# Robot_Board_v001.net
KiCad netlist of a schematic drawn in EAGLE
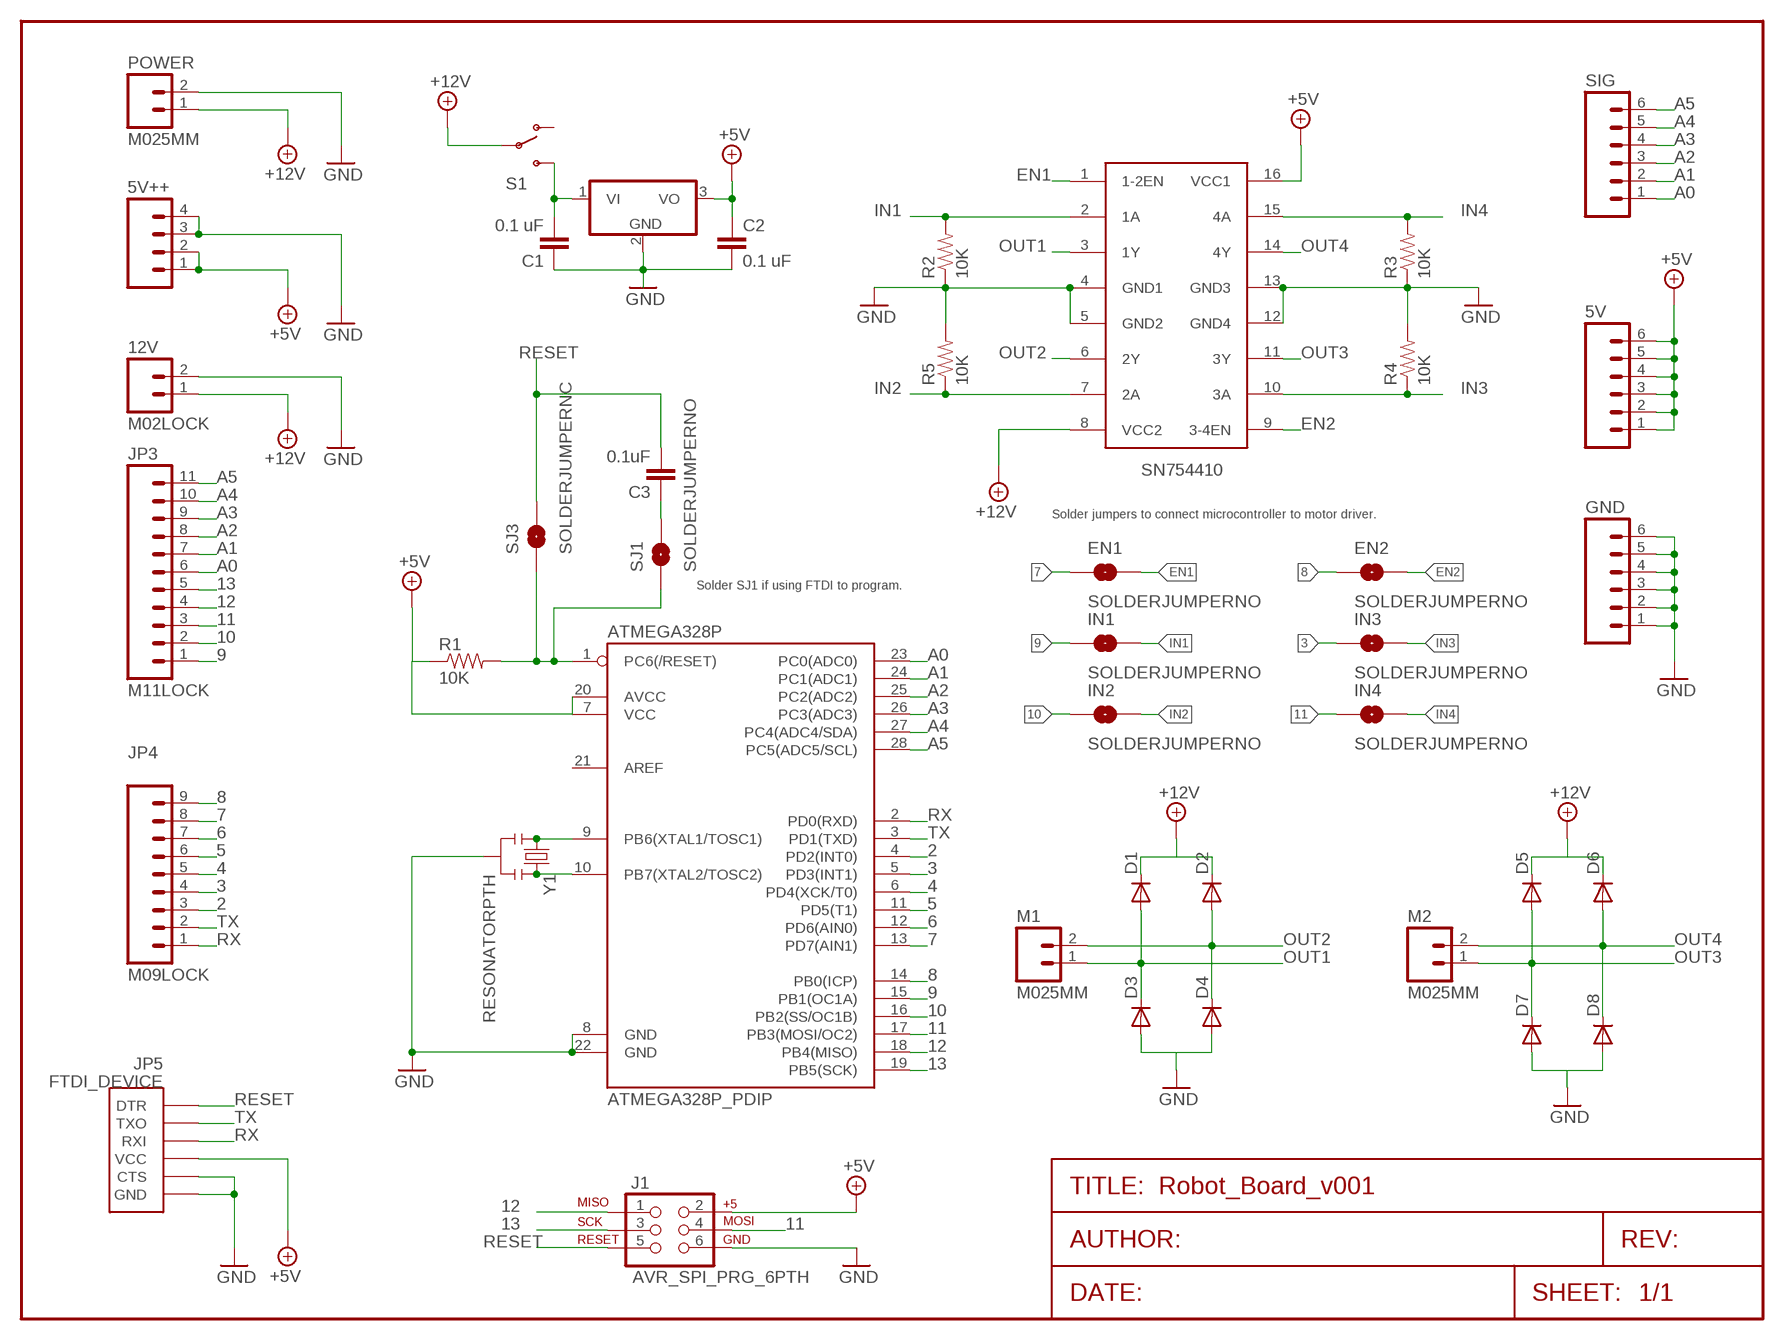
[diagram p0: schematic, sheet 1]

(export (version "E")
  (design (tool "Eeschema 10.0.6"))
  (components
    (comp (ref "5V")
      (value "M06SIP")
      (footprint "eagle-import:1X06")
      (libsource (lib "eagle-import") (part "M06SIP"))
    )
    (comp (ref "5V++")
      (value "M04LOCK")
      (footprint "eagle-import:1X04_LOCK")
      (libsource (lib "eagle-import") (part "M04LOCK"))
    )
    (comp (ref "12V")
      (value "M02LOCK")
      (footprint "eagle-import:1X02_LOCK")
      (libsource (lib "eagle-import") (part "M02LOCK"))
    )
    (comp (ref "7805")
      (value "7805TV")
      (footprint "eagle-import:TO220V")
      (libsource (lib "eagle-import") (part "78TV05"))
    )
    (comp (ref "ATMEGA328P")
      (value "ATMEGA328P_PDIP")
      (footprint "eagle-import:DIL28-3")
      (libsource (lib "eagle-import") (part "ATMEGA328P_PDIP"))
    )
    (comp (ref "C1")
      (value "0.1 uF")
      (footprint "eagle-import:CAP-PTH-5MM")
      (libsource (lib "eagle-import") (part "CAPPTH1"))
    )
    (comp (ref "C2")
      (value "0.1 uF")
      (footprint "eagle-import:CAP-PTH-5MM")
      (libsource (lib "eagle-import") (part "CAPPTH1"))
    )
    (comp (ref "C3")
      (value "0.1uF")
      (footprint "eagle-import:CAP-PTH-5MM")
      (libsource (lib "eagle-import") (part "CAPPTH1"))
    )
    (comp (ref "D1")
      (value "DIODEPTH")
      (footprint "eagle-import:DIODE-1N4001")
      (libsource (lib "eagle-import") (part "DIODEPTH"))
    )
    (comp (ref "D2")
      (value "DIODEPTH")
      (footprint "eagle-import:DIODE-1N4001")
      (libsource (lib "eagle-import") (part "DIODEPTH"))
    )
    (comp (ref "D3")
      (value "DIODEPTH")
      (footprint "eagle-import:DIODE-1N4001")
      (libsource (lib "eagle-import") (part "DIODEPTH"))
    )
    (comp (ref "D4")
      (value "DIODEPTH")
      (footprint "eagle-import:DIODE-1N4001")
      (libsource (lib "eagle-import") (part "DIODEPTH"))
    )
    (comp (ref "D5")
      (value "DIODEPTH")
      (footprint "eagle-import:DIODE-1N4001")
      (libsource (lib "eagle-import") (part "DIODEPTH"))
    )
    (comp (ref "D6")
      (value "DIODEPTH")
      (footprint "eagle-import:DIODE-1N4001")
      (libsource (lib "eagle-import") (part "DIODEPTH"))
    )
    (comp (ref "D7")
      (value "DIODEPTH")
      (footprint "eagle-import:DIODE-1N4001")
      (libsource (lib "eagle-import") (part "DIODEPTH"))
    )
    (comp (ref "D8")
      (value "DIODEPTH")
      (footprint "eagle-import:DIODE-1N4001")
      (libsource (lib "eagle-import") (part "DIODEPTH"))
    )
    (comp (ref "EN1")
      (value "SOLDERJUMPERNO")
      (footprint "eagle-import:SJ_2S-NO")
      (libsource (lib "eagle-import") (part "SOLDERJUMPERNO"))
    )
    (comp (ref "EN2")
      (value "SOLDERJUMPERNO")
      (footprint "eagle-import:SJ_2S-NO")
      (libsource (lib "eagle-import") (part "SOLDERJUMPERNO"))
    )
    (comp (ref "GND")
      (value "M06SIP")
      (footprint "eagle-import:1X06")
      (libsource (lib "eagle-import") (part "M06SIP"))
    )
    (comp (ref "IN1")
      (value "SOLDERJUMPERNO")
      (footprint "eagle-import:SJ_2S-NO")
      (libsource (lib "eagle-import") (part "SOLDERJUMPERNO"))
    )
    (comp (ref "IN2")
      (value "SOLDERJUMPERNO")
      (footprint "eagle-import:SJ_2S-NO")
      (libsource (lib "eagle-import") (part "SOLDERJUMPERNO"))
    )
    (comp (ref "IN3")
      (value "SOLDERJUMPERNO")
      (footprint "eagle-import:SJ_2S-NO")
      (libsource (lib "eagle-import") (part "SOLDERJUMPERNO"))
    )
    (comp (ref "IN4")
      (value "SOLDERJUMPERNO")
      (footprint "eagle-import:SJ_2S-NO")
      (libsource (lib "eagle-import") (part "SOLDERJUMPERNO"))
    )
    (comp (ref "J1")
      (value "AVR_SPI_PRG_6PTH")
      (footprint "eagle-import:2X3")
      (libsource (lib "eagle-import") (part "AVR_SPI_PRG_6PTH"))
    )
    (comp (ref "JP3")
      (value "M11LOCK")
      (footprint "eagle-import:1X11_LOCK")
      (libsource (lib "eagle-import") (part "M11LOCK"))
    )
    (comp (ref "JP4")
      (value "M09LOCK")
      (footprint "eagle-import:1X09_LOCK")
      (libsource (lib "eagle-import") (part "M09LOCK"))
    )
    (comp (ref "JP5")
      (value "FTDI_DEVICE")
      (footprint "eagle-import:FTDI_DEVICE_SIDE")
      (libsource (lib "eagle-import") (part "FTDI_DEVICE"))
    )
    (comp (ref "M1")
      (value "M025MM")
      (footprint "eagle-import:SCREWTERMINAL-5MM-2")
      (libsource (lib "eagle-import") (part "M025MM"))
    )
    (comp (ref "M2")
      (value "M025MM")
      (footprint "eagle-import:SCREWTERMINAL-5MM-2")
      (libsource (lib "eagle-import") (part "M025MM"))
    )
    (comp (ref "POWER")
      (value "M025MM")
      (footprint "eagle-import:SCREWTERMINAL-5MM-2")
      (libsource (lib "eagle-import") (part "M025MM"))
    )
    (comp (ref "R1")
      (value "10K")
      (footprint "eagle-import:AXIAL-0.4")
      (libsource (lib "eagle-import") (part "RESISTORPTH-1/4W"))
    )
    (comp (ref "R2")
      (value "10K")
      (footprint "eagle-import:AXIAL-0.4")
      (libsource (lib "eagle-import") (part "RESISTORPTH-1/4W"))
    )
    (comp (ref "R3")
      (value "10K")
      (footprint "eagle-import:AXIAL-0.4")
      (libsource (lib "eagle-import") (part "RESISTORPTH-1/4W"))
    )
    (comp (ref "R4")
      (value "10K")
      (footprint "eagle-import:AXIAL-0.4")
      (libsource (lib "eagle-import") (part "RESISTORPTH-1/4W"))
    )
    (comp (ref "R5")
      (value "10K")
      (footprint "eagle-import:AXIAL-0.4")
      (libsource (lib "eagle-import") (part "RESISTORPTH-1/4W"))
    )
    (comp (ref "S1")
      (value "SWITCH-SPDTPTH")
      (footprint "eagle-import:SWITCH-SPDT")
      (libsource (lib "eagle-import") (part "SWITCH-SPDTPTH"))
    )
    (comp (ref "SIG")
      (value "M06SIP")
      (footprint "eagle-import:1X06")
      (libsource (lib "eagle-import") (part "M06SIP"))
    )
    (comp (ref "SJ1")
      (value "SOLDERJUMPERNO")
      (footprint "eagle-import:SJ_2S-NO")
      (libsource (lib "eagle-import") (part "SOLDERJUMPERNO"))
    )
    (comp (ref "SJ3")
      (value "SOLDERJUMPERNC")
      (footprint "eagle-import:SJ_2S")
      (libsource (lib "eagle-import") (part "SOLDERJUMPERNC"))
    )
    (comp (ref "SN754410")
      (value "L293D")
      (footprint "eagle-import:DIL16")
      (libsource (lib "eagle-import") (part "L293D"))
    )
    (comp (ref "Y1")
      (value "RESONATORPTH")
      (footprint "eagle-import:RESONATOR-PTH")
      (libsource (lib "eagle-import") (part "RESONATORPTH"))
    )
  )
  (nets
    (net (code "1") (name "+5V") (class "Default")
      (node (ref "5V") (pin "1") (pinfunction "1_1") (pintype "passive"))
      (node (ref "5V") (pin "2") (pinfunction "2_2") (pintype "passive"))
      (node (ref "5V") (pin "3") (pinfunction "3_3") (pintype "passive"))
      (node (ref "5V") (pin "4") (pinfunction "4_4") (pintype "passive"))
      (node (ref "5V") (pin "5") (pinfunction "5_5") (pintype "passive"))
      (node (ref "5V") (pin "6") (pinfunction "6_6") (pintype "passive"))
      (node (ref "5V++") (pin "1") (pinfunction "1_1") (pintype "passive"))
      (node (ref "5V++") (pin "2") (pinfunction "2_2") (pintype "passive"))
      (node (ref "7805") (pin "3") (pinfunction "VO_3") (pintype "passive"))
      (node (ref "ATMEGA328P") (pin "20") (pinfunction "AVCC_20") (pintype "bidirectional"))
      (node (ref "ATMEGA328P") (pin "7") (pinfunction "VCC_7") (pintype "bidirectional"))
      (node (ref "C2") (pin "1") (pinfunction "1_1") (pintype "passive"))
      (node (ref "J1") (pin "2") (pinfunction "2_2") (pintype "passive"))
      (node (ref "JP5") (pin "P$4") (pinfunction "VCC_P$4") (pintype "bidirectional"))
      (node (ref "R1") (pin "P$1") (pinfunction "1_P$1") (pintype "passive"))
      (node (ref "SN754410") (pin "16") (pinfunction "VCC1_16") (pintype "power_in"))
    )
    (net (code "2") (name "+12V") (class "Default")
      (node (ref "12V") (pin "1") (pinfunction "1_1") (pintype "passive"))
      (node (ref "D1") (pin "C") (pinfunction "C_C") (pintype "passive"))
      (node (ref "D2") (pin "C") (pinfunction "C_C") (pintype "passive"))
      (node (ref "D5") (pin "C") (pinfunction "C_C") (pintype "passive"))
      (node (ref "D6") (pin "C") (pinfunction "C_C") (pintype "passive"))
      (node (ref "POWER") (pin "1") (pinfunction "1_1") (pintype "passive"))
      (node (ref "S1") (pin "2") (pinfunction "P_2") (pintype "passive"))
      (node (ref "SN754410") (pin "8") (pinfunction "VCC2_8") (pintype "power_in"))
    )
    (net (code "3") (name "/2") (class "Default")
      (node (ref "ATMEGA328P") (pin "4") (pinfunction "PD2(INT0)_4") (pintype "bidirectional"))
      (node (ref "JP4") (pin "3") (pinfunction "3_3") (pintype "passive"))
    )
    (net (code "4") (name "/4") (class "Default")
      (node (ref "ATMEGA328P") (pin "6") (pinfunction "PD4(XCK/T0)_6") (pintype "bidirectional"))
      (node (ref "JP4") (pin "5") (pinfunction "5_5") (pintype "passive"))
    )
    (net (code "5") (name "/5") (class "Default")
      (node (ref "ATMEGA328P") (pin "11") (pinfunction "PD5(T1)_11") (pintype "bidirectional"))
      (node (ref "JP4") (pin "6") (pinfunction "6_6") (pintype "passive"))
    )
    (net (code "6") (name "/6") (class "Default")
      (node (ref "ATMEGA328P") (pin "12") (pinfunction "PD6(AIN0)_12") (pintype "bidirectional"))
      (node (ref "JP4") (pin "7") (pinfunction "7_7") (pintype "passive"))
    )
    (net (code "7") (name "/12") (class "Default")
      (node (ref "ATMEGA328P") (pin "18") (pinfunction "PB4(MISO)_18") (pintype "bidirectional"))
      (node (ref "J1") (pin "1") (pinfunction "1_1") (pintype "passive"))
      (node (ref "JP3") (pin "4") (pinfunction "4_4") (pintype "passive"))
    )
    (net (code "8") (name "/13") (class "Default")
      (node (ref "ATMEGA328P") (pin "19") (pinfunction "PB5(SCK)_19") (pintype "bidirectional"))
      (node (ref "J1") (pin "3") (pinfunction "3_3") (pintype "passive"))
      (node (ref "JP3") (pin "5") (pinfunction "5_5") (pintype "passive"))
    )
    (net (code "9") (name "/A0") (class "Default")
      (node (ref "ATMEGA328P") (pin "23") (pinfunction "PC0(ADC0)_23") (pintype "bidirectional"))
      (node (ref "JP3") (pin "6") (pinfunction "6_6") (pintype "passive"))
      (node (ref "SIG") (pin "1") (pinfunction "1_1") (pintype "passive"))
    )
    (net (code "10") (name "/A1") (class "Default")
      (node (ref "ATMEGA328P") (pin "24") (pinfunction "PC1(ADC1)_24") (pintype "bidirectional"))
      (node (ref "JP3") (pin "7") (pinfunction "7_7") (pintype "passive"))
      (node (ref "SIG") (pin "2") (pinfunction "2_2") (pintype "passive"))
    )
    (net (code "11") (name "/A2") (class "Default")
      (node (ref "ATMEGA328P") (pin "25") (pinfunction "PC2(ADC2)_25") (pintype "bidirectional"))
      (node (ref "JP3") (pin "8") (pinfunction "8_8") (pintype "passive"))
      (node (ref "SIG") (pin "3") (pinfunction "3_3") (pintype "passive"))
    )
    (net (code "12") (name "/A3") (class "Default")
      (node (ref "ATMEGA328P") (pin "26") (pinfunction "PC3(ADC3)_26") (pintype "bidirectional"))
      (node (ref "JP3") (pin "9") (pinfunction "9_9") (pintype "passive"))
      (node (ref "SIG") (pin "4") (pinfunction "4_4") (pintype "passive"))
    )
    (net (code "13") (name "/A4") (class "Default")
      (node (ref "ATMEGA328P") (pin "27") (pinfunction "PC4(ADC4/SDA)_27") (pintype "bidirectional"))
      (node (ref "JP3") (pin "10") (pinfunction "10_10") (pintype "passive"))
      (node (ref "SIG") (pin "5") (pinfunction "5_5") (pintype "passive"))
    )
    (net (code "14") (name "/A5") (class "Default")
      (node (ref "ATMEGA328P") (pin "28") (pinfunction "PC5(ADC5/SCL)_28") (pintype "bidirectional"))
      (node (ref "JP3") (pin "11") (pinfunction "11_11") (pintype "passive"))
      (node (ref "SIG") (pin "6") (pinfunction "6_6") (pintype "passive"))
    )
    (net (code "15") (name "/OUT1") (class "Default")
      (node (ref "D1") (pin "A") (pinfunction "A_A") (pintype "passive"))
      (node (ref "D3") (pin "C") (pinfunction "C_C") (pintype "passive"))
      (node (ref "M1") (pin "1") (pinfunction "1_1") (pintype "passive"))
      (node (ref "SN754410") (pin "3") (pinfunction "1Y_3") (pintype "output"))
    )
    (net (code "16") (name "/OUT2") (class "Default")
      (node (ref "D2") (pin "A") (pinfunction "A_A") (pintype "passive"))
      (node (ref "D4") (pin "C") (pinfunction "C_C") (pintype "passive"))
      (node (ref "M1") (pin "2") (pinfunction "2_2") (pintype "passive"))
      (node (ref "SN754410") (pin "6") (pinfunction "2Y_6") (pintype "output"))
    )
    (net (code "17") (name "/OUT3") (class "Default")
      (node (ref "D5") (pin "A") (pinfunction "A_A") (pintype "passive"))
      (node (ref "D7") (pin "C") (pinfunction "C_C") (pintype "passive"))
      (node (ref "M2") (pin "1") (pinfunction "1_1") (pintype "passive"))
      (node (ref "SN754410") (pin "11") (pinfunction "3Y_11") (pintype "output"))
    )
    (net (code "18") (name "/OUT4") (class "Default")
      (node (ref "D6") (pin "A") (pinfunction "A_A") (pintype "passive"))
      (node (ref "D8") (pin "C") (pinfunction "C_C") (pintype "passive"))
      (node (ref "M2") (pin "2") (pinfunction "2_2") (pintype "passive"))
      (node (ref "SN754410") (pin "14") (pinfunction "4Y_14") (pintype "output"))
    )
    (net (code "19") (name "/RESET") (class "Default")
      (node (ref "C3") (pin "2") (pinfunction "2_2") (pintype "passive"))
      (node (ref "J1") (pin "5") (pinfunction "5_5") (pintype "passive"))
      (node (ref "JP5") (pin "P$1") (pinfunction "DTR_P$1") (pintype "bidirectional"))
      (node (ref "SJ3") (pin "2") (pinfunction "2_2") (pintype "passive"))
    )
    (net (code "20") (name "/RX") (class "Default")
      (node (ref "ATMEGA328P") (pin "2") (pinfunction "PD0(RXD)_2") (pintype "bidirectional"))
      (node (ref "JP4") (pin "1") (pinfunction "1_1") (pintype "passive"))
      (node (ref "JP5") (pin "P$3") (pinfunction "RXI_P$3") (pintype "bidirectional"))
    )
    (net (code "21") (name "/TX") (class "Default")
      (node (ref "ATMEGA328P") (pin "3") (pinfunction "PD1(TXD)_3") (pintype "bidirectional"))
      (node (ref "JP4") (pin "2") (pinfunction "2_2") (pintype "passive"))
      (node (ref "JP5") (pin "P$2") (pinfunction "TXO_P$2") (pintype "bidirectional"))
    )
    (net (code "22") (name "3") (class "Default")
      (node (ref "ATMEGA328P") (pin "5") (pinfunction "PD3(INT1)_5") (pintype "bidirectional"))
      (node (ref "IN3") (pin "1") (pinfunction "1_1") (pintype "passive"))
      (node (ref "JP4") (pin "4") (pinfunction "4_4") (pintype "passive"))
    )
    (net (code "23") (name "7") (class "Default")
      (node (ref "ATMEGA328P") (pin "13") (pinfunction "PD7(AIN1)_13") (pintype "bidirectional"))
      (node (ref "EN1") (pin "1") (pinfunction "1_1") (pintype "passive"))
      (node (ref "JP4") (pin "8") (pinfunction "8_8") (pintype "passive"))
    )
    (net (code "24") (name "8") (class "Default")
      (node (ref "ATMEGA328P") (pin "14") (pinfunction "PB0(ICP)_14") (pintype "bidirectional"))
      (node (ref "EN2") (pin "1") (pinfunction "1_1") (pintype "passive"))
      (node (ref "JP4") (pin "9") (pinfunction "9_9") (pintype "passive"))
    )
    (net (code "25") (name "9") (class "Default")
      (node (ref "ATMEGA328P") (pin "15") (pinfunction "PB1(OC1A)_15") (pintype "bidirectional"))
      (node (ref "IN1") (pin "1") (pinfunction "1_1") (pintype "passive"))
      (node (ref "JP3") (pin "1") (pinfunction "1_1") (pintype "passive"))
    )
    (net (code "26") (name "10") (class "Default")
      (node (ref "ATMEGA328P") (pin "16") (pinfunction "PB2(SS/OC1B)_16") (pintype "bidirectional"))
      (node (ref "IN2") (pin "1") (pinfunction "1_1") (pintype "passive"))
      (node (ref "JP3") (pin "2") (pinfunction "2_2") (pintype "passive"))
    )
    (net (code "27") (name "11") (class "Default")
      (node (ref "ATMEGA328P") (pin "17") (pinfunction "PB3(MOSI/OC2)_17") (pintype "bidirectional"))
      (node (ref "IN4") (pin "1") (pinfunction "1_1") (pintype "passive"))
      (node (ref "J1") (pin "4") (pinfunction "4_4") (pintype "passive"))
      (node (ref "JP3") (pin "3") (pinfunction "3_3") (pintype "passive"))
    )
    (net (code "28") (name "EN1") (class "Default")
      (node (ref "EN1") (pin "2") (pinfunction "2_2") (pintype "passive"))
      (node (ref "SN754410") (pin "1") (pinfunction "1-2EN_1") (pintype "input"))
    )
    (net (code "29") (name "EN2") (class "Default")
      (node (ref "EN2") (pin "2") (pinfunction "2_2") (pintype "passive"))
      (node (ref "SN754410") (pin "9") (pinfunction "3-4EN_9") (pintype "input"))
    )
    (net (code "30") (name "GND") (class "Default")
      (node (ref "12V") (pin "2") (pinfunction "2_2") (pintype "passive"))
      (node (ref "5V++") (pin "3") (pinfunction "3_3") (pintype "passive"))
      (node (ref "5V++") (pin "4") (pinfunction "4_4") (pintype "passive"))
      (node (ref "7805") (pin "2") (pinfunction "GND_2") (pintype "passive"))
      (node (ref "ATMEGA328P") (pin "22") (pinfunction "GND_22") (pintype "bidirectional"))
      (node (ref "ATMEGA328P") (pin "8") (pinfunction "GND_8") (pintype "bidirectional"))
      (node (ref "C1") (pin "1") (pinfunction "1_1") (pintype "passive"))
      (node (ref "C2") (pin "2") (pinfunction "2_2") (pintype "passive"))
      (node (ref "D3") (pin "A") (pinfunction "A_A") (pintype "passive"))
      (node (ref "D4") (pin "A") (pinfunction "A_A") (pintype "passive"))
      (node (ref "D7") (pin "A") (pinfunction "A_A") (pintype "passive"))
      (node (ref "D8") (pin "A") (pinfunction "A_A") (pintype "passive"))
      (node (ref "GND") (pin "1") (pinfunction "1_1") (pintype "passive"))
      (node (ref "GND") (pin "2") (pinfunction "2_2") (pintype "passive"))
      (node (ref "GND") (pin "3") (pinfunction "3_3") (pintype "passive"))
      (node (ref "GND") (pin "4") (pinfunction "4_4") (pintype "passive"))
      (node (ref "GND") (pin "5") (pinfunction "5_5") (pintype "passive"))
      (node (ref "GND") (pin "6") (pinfunction "6_6") (pintype "passive"))
      (node (ref "J1") (pin "6") (pinfunction "6_6") (pintype "passive"))
      (node (ref "JP5") (pin "P$5") (pinfunction "CTS_P$5") (pintype "bidirectional"))
      (node (ref "JP5") (pin "P$6") (pinfunction "GND_P$6") (pintype "bidirectional"))
      (node (ref "POWER") (pin "2") (pinfunction "2_2") (pintype "passive"))
      (node (ref "R2") (pin "P$1") (pinfunction "1_P$1") (pintype "passive"))
      (node (ref "R3") (pin "P$1") (pinfunction "1_P$1") (pintype "passive"))
      (node (ref "R4") (pin "P$2") (pinfunction "2_P$2") (pintype "passive"))
      (node (ref "R5") (pin "P$2") (pinfunction "2_P$2") (pintype "passive"))
      (node (ref "SN754410") (pin "12") (pinfunction "GND4_12") (pintype "power_in"))
      (node (ref "SN754410") (pin "13") (pinfunction "GND3_13") (pintype "power_in"))
      (node (ref "SN754410") (pin "4") (pinfunction "GND1_4") (pintype "power_in"))
      (node (ref "SN754410") (pin "5") (pinfunction "GND2_5") (pintype "power_in"))
      (node (ref "Y1") (pin "2") (pinfunction "2_2") (pintype "passive"))
    )
    (net (code "31") (name "IN1") (class "Default")
      (node (ref "IN1") (pin "2") (pinfunction "2_2") (pintype "passive"))
      (node (ref "R2") (pin "P$2") (pinfunction "2_P$2") (pintype "passive"))
      (node (ref "SN754410") (pin "2") (pinfunction "1A_2") (pintype "input"))
    )
    (net (code "32") (name "IN2") (class "Default")
      (node (ref "IN2") (pin "2") (pinfunction "2_2") (pintype "passive"))
      (node (ref "R5") (pin "P$1") (pinfunction "1_P$1") (pintype "passive"))
      (node (ref "SN754410") (pin "7") (pinfunction "2A_7") (pintype "input"))
    )
    (net (code "33") (name "IN3") (class "Default")
      (node (ref "IN3") (pin "2") (pinfunction "2_2") (pintype "passive"))
      (node (ref "R4") (pin "P$1") (pinfunction "1_P$1") (pintype "passive"))
      (node (ref "SN754410") (pin "10") (pinfunction "3A_10") (pintype "input"))
    )
    (net (code "34") (name "IN4") (class "Default")
      (node (ref "IN4") (pin "2") (pinfunction "2_2") (pintype "passive"))
      (node (ref "R3") (pin "P$2") (pinfunction "2_P$2") (pintype "passive"))
      (node (ref "SN754410") (pin "15") (pinfunction "4A_15") (pintype "input"))
    )
    (net (code "35") (name "Net-(7805-VI)") (class "Default")
      (node (ref "7805") (pin "1") (pinfunction "VI_1") (pintype "input"))
      (node (ref "C1") (pin "2") (pinfunction "2_2") (pintype "passive"))
      (node (ref "S1") (pin "3") (pinfunction "S_3") (pintype "passive"))
    )
    (net (code "36") (name "Net-(ATMEGA328P-PB6(XTAL1{slash}TOSC1))") (class "Default")
      (node (ref "ATMEGA328P") (pin "9") (pinfunction "PB6(XTAL1/TOSC1)_9") (pintype "bidirectional"))
      (node (ref "Y1") (pin "1") (pinfunction "1_1") (pintype "passive"))
    )
    (net (code "37") (name "Net-(ATMEGA328P-PB7(XTAL2{slash}TOSC2))") (class "Default")
      (node (ref "ATMEGA328P") (pin "10") (pinfunction "PB7(XTAL2/TOSC2)_10") (pintype "bidirectional"))
      (node (ref "Y1") (pin "3") (pinfunction "3_3") (pintype "passive"))
    )
    (net (code "38") (name "Net-(ATMEGA328P-PC6({slash}RESET))") (class "Default")
      (node (ref "ATMEGA328P") (pin "1") (pinfunction "PC6(/RESET)_1") (pintype "bidirectional"))
      (node (ref "R1") (pin "P$2") (pinfunction "2_P$2") (pintype "passive"))
      (node (ref "SJ1") (pin "1") (pinfunction "1_1") (pintype "passive"))
      (node (ref "SJ3") (pin "1") (pinfunction "1_1") (pintype "passive"))
    )
    (net (code "39") (name "Net-(C3-Pad1)") (class "Default")
      (node (ref "C3") (pin "1") (pinfunction "1_1") (pintype "passive"))
      (node (ref "SJ1") (pin "2") (pinfunction "2_2") (pintype "passive"))
    )
    (net (code "40") (name "unconnected-(ATMEGA328P-AREF-Pad21)") (class "Default")
      (node (ref "ATMEGA328P") (pin "21") (pinfunction "AREF_21") (pintype "bidirectional"))
    )
    (net (code "41") (name "unconnected-(S1-O-Pad1)") (class "Default")
      (node (ref "S1") (pin "1") (pinfunction "O_1") (pintype "passive"))
    )
  )
)
